# PCB_Preamp_5.net
KiCad netlist of a schematic drawn in EasyEDA Pro
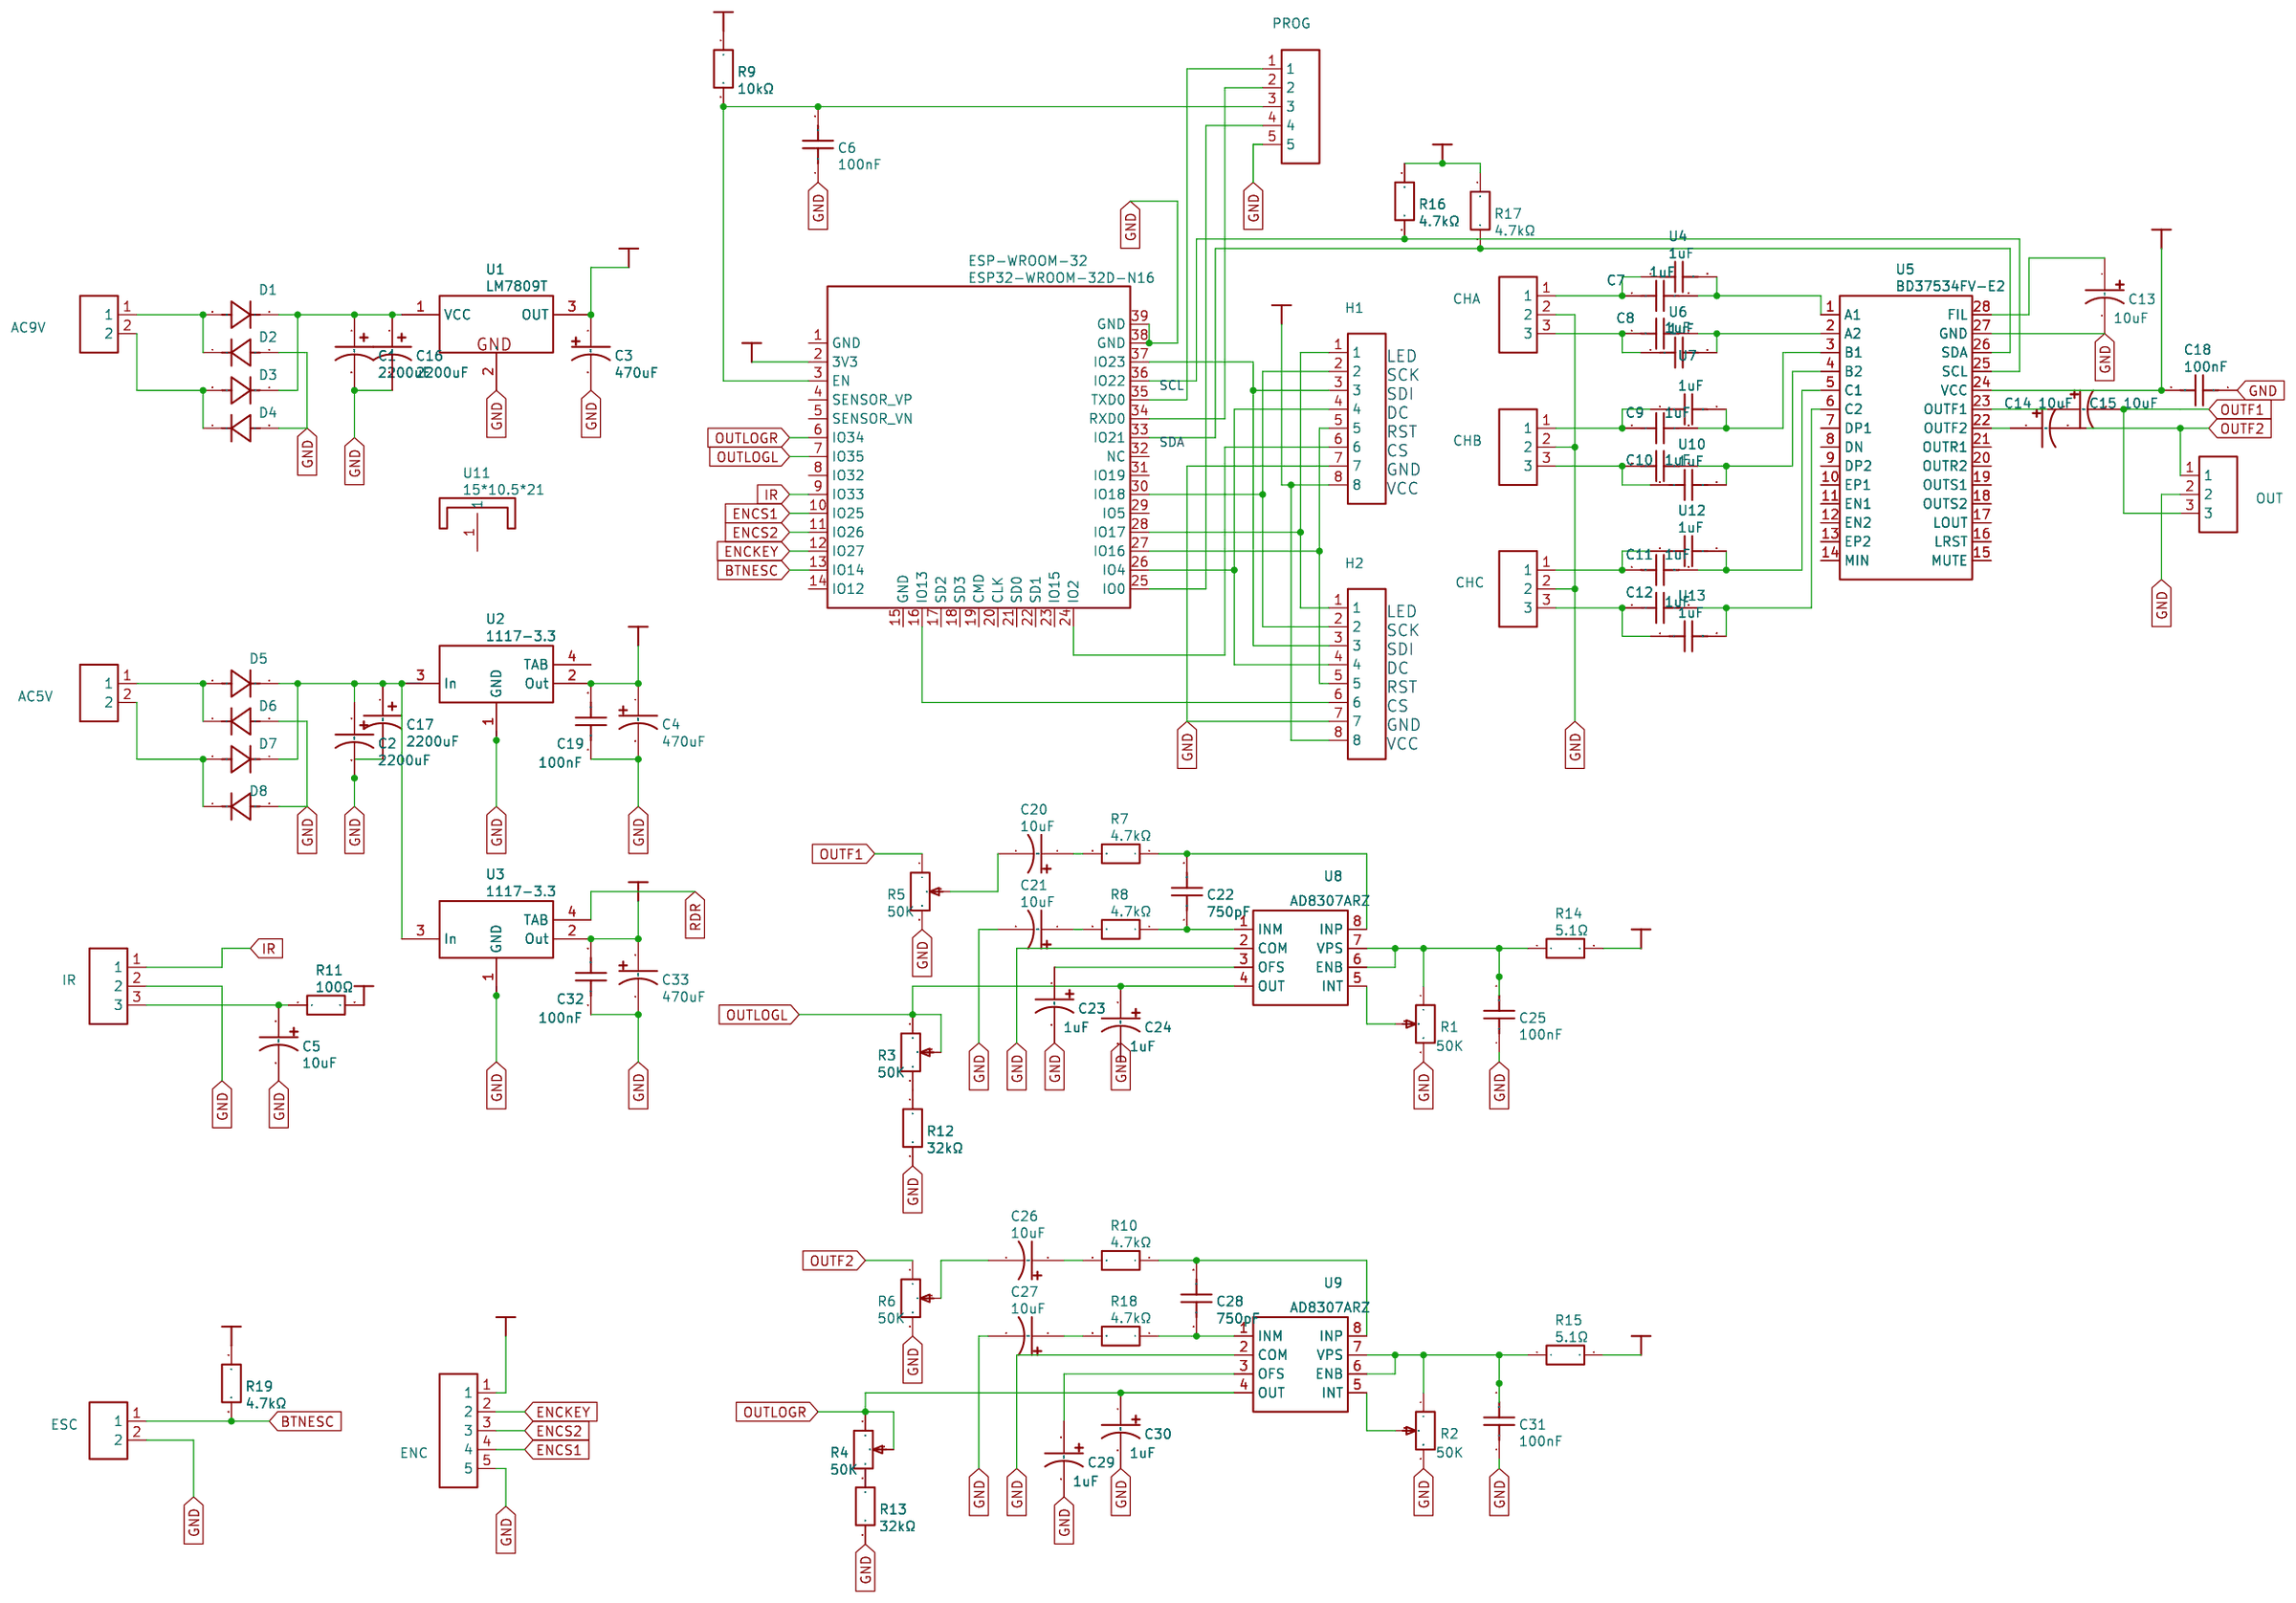
[diagram p0: schematic sheet]

(export (version "E")
  (design (tool "Eeschema 10.0.6"))
  (components
    (comp (ref "AC5V")
      (value "DB126V-5.0-2P")
      (footprint "easyedapro:CONN-TH_2P-P5.00_L7.8-W10.0")
      (fields
        (field (name "Manufacturer Part") "DB126V-5.0-2P-GN-P")
        (field (name "Manufacturer") "DORABO(地博电气)")
      )
      (libsource (lib "easyedapro") (part "DB126V-5.0-2P"))
    )
    (comp (ref "AC9V")
      (value "DB126V-5.0-2P")
      (footprint "easyedapro:CONN-TH_2P-P5.00_L7.8-W10.0")
      (fields
        (field (name "Manufacturer Part") "DB126V-5.0-2P-GN-P")
        (field (name "Manufacturer") "DORABO(地博电气)")
      )
      (libsource (lib "easyedapro") (part "DB126V-5.0-2P"))
    )
    (comp (ref "C1")
      (value "2200uF")
      (footprint "easyedapro:CAP-TH_BD12.5-P5.00-D0.6-FD")
      (fields
        (field (name "Manufacturer Part") "16YXG2200MLLCCE12.5X25")
        (field (name "Manufacturer") "rubycon(红宝石)")
      )
      (libsource (lib "easyedapro") (part "2200uF"))
    )
    (comp (ref "C2")
      (value "2200uF")
      (footprint "easyedapro:CAP-TH_BD12.5-P5.00-D0.6-FD")
      (fields
        (field (name "Manufacturer Part") "16YXG2200MLLCCE12.5X25")
        (field (name "Manufacturer") "rubycon(红宝石)")
      )
      (libsource (lib "easyedapro") (part "2200uF"))
    )
    (comp (ref "C3")
      (value "470uF")
      (footprint "easyedapro:CAP-TH_BD8.0-P3.50-D0.6-FD")
      (fields (field (name "Manufacturer Part") "EHRL474M016F12BC") (field (name "Manufacturer") "HEAO(和澳)"))
      (libsource (lib "easyedapro") (part "470uF"))
    )
    (comp (ref "C4")
      (value "470uF")
      (footprint "easyedapro:CAP-TH_BD8.0-P3.50-D0.6-FD")
      (fields (field (name "Manufacturer Part") "EHRL474M016F12BC") (field (name "Manufacturer") "HEAO(和澳)"))
      (libsource (lib "easyedapro") (part "470uF"))
    )
    (comp (ref "C5")
      (value "10uF")
      (footprint "easyedapro:CAP-TH_BD5.0-P2.00-D0.5-FD")
      (fields (field (name "Manufacturer Part") "35ZLJ47M5X11") (field (name "Manufacturer") "rubycon(红宝石)"))
      (libsource (lib "easyedapro") (part "10uF"))
    )
    (comp (ref "C6")
      (value "100nF")
      (footprint "easyedapro:CAP-TH_L7.2-W2.5-P5.00-D0.6")
      (fields (field (name "Manufacturer Part") "BFC237011104") (field (name "Manufacturer") "VISHAY(威世)"))
      (libsource (lib "easyedapro") (part "100nF"))
    )
    (comp (ref "C7")
      (value "1uF")
      (footprint "easyedapro:CAP-TH_L13.0-W6.0-P10.00-D0.6")
      (fields (field (name "Manufacturer Part") "B32521C1105J") (field (name "Manufacturer") "TDK"))
      (libsource (lib "") (part "1uF_1"))
    )
    (comp (ref "C8")
      (value "1uF")
      (footprint "easyedapro:CAP-TH_L13.0-W6.0-P10.00-D0.6")
      (fields (field (name "Manufacturer Part") "B32521C1105J") (field (name "Manufacturer") "TDK"))
      (libsource (lib "") (part "1uF_1"))
    )
    (comp (ref "C9")
      (value "1uF")
      (footprint "easyedapro:CAP-TH_L13.0-W6.0-P10.00-D0.6")
      (fields (field (name "Manufacturer Part") "B32521C1105J") (field (name "Manufacturer") "TDK"))
      (libsource (lib "") (part "1uF_1"))
    )
    (comp (ref "C10")
      (value "1uF")
      (footprint "easyedapro:CAP-TH_L13.0-W6.0-P10.00-D0.6")
      (fields (field (name "Manufacturer Part") "B32521C1105J") (field (name "Manufacturer") "TDK"))
      (libsource (lib "") (part "1uF_1"))
    )
    (comp (ref "C11")
      (value "1uF")
      (footprint "easyedapro:CAP-TH_L13.0-W6.0-P10.00-D0.6")
      (fields (field (name "Manufacturer Part") "B32521C1105J") (field (name "Manufacturer") "TDK"))
      (libsource (lib "") (part "1uF_1"))
    )
    (comp (ref "C12")
      (value "1uF")
      (footprint "easyedapro:CAP-TH_L13.0-W6.0-P10.00-D0.6")
      (fields (field (name "Manufacturer Part") "B32521C1105J") (field (name "Manufacturer") "TDK"))
      (libsource (lib "") (part "1uF_1"))
    )
    (comp (ref "C13")
      (value "10uF")
      (footprint "easyedapro:CAP-TH_BD5.0-P2.00-D0.5-FD")
      (fields (field (name "Manufacturer Part") "35ZLJ47M5X11") (field (name "Manufacturer") "rubycon(红宝石)"))
      (libsource (lib "easyedapro") (part "10uF"))
    )
    (comp (ref "C14")
      (value "10uF")
      (footprint "easyedapro:CAP-TH_BD5.0-P2.00-D0.5-FD")
      (fields (field (name "Manufacturer Part") "35ZLJ47M5X11") (field (name "Manufacturer") "rubycon(红宝石)"))
      (libsource (lib "") (part "10uF_1"))
    )
    (comp (ref "C15")
      (value "10uF")
      (footprint "easyedapro:CAP-TH_BD5.0-P2.00-D0.5-FD")
      (fields (field (name "Manufacturer Part") "35ZLJ47M5X11") (field (name "Manufacturer") "rubycon(红宝石)"))
      (libsource (lib "") (part "10uF_1"))
    )
    (comp (ref "C16")
      (value "2200uF")
      (footprint "easyedapro:CAP-TH_BD12.5-P5.00-D0.6-FD")
      (fields
        (field (name "Manufacturer Part") "16YXG2200MLLCCE12.5X25")
        (field (name "Manufacturer") "rubycon(红宝石)")
      )
      (libsource (lib "easyedapro") (part "2200uF"))
    )
    (comp (ref "C17")
      (value "2200uF")
      (footprint "easyedapro:CAP-TH_BD12.5-P5.00-D0.6-FD")
      (fields
        (field (name "Manufacturer Part") "16YXG2200MLLCCE12.5X25")
        (field (name "Manufacturer") "rubycon(红宝石)")
      )
      (libsource (lib "easyedapro") (part "2200uF"))
    )
    (comp (ref "C18")
      (value "100nF")
      (footprint "easyedapro:CAP-TH_L7.2-W2.5-P5.00-D0.6")
      (fields (field (name "Manufacturer Part") "BFC237011104") (field (name "Manufacturer") "VISHAY(威世)"))
      (libsource (lib "easyedapro") (part "100nF"))
    )
    (comp (ref "C19")
      (value "100nF")
      (footprint "easyedapro:CAP-TH_L7.2-W2.5-P5.00-D0.6")
      (fields (field (name "Manufacturer Part") "BFC237011104") (field (name "Manufacturer") "VISHAY(威世)"))
      (libsource (lib "easyedapro") (part "100nF"))
    )
    (comp (ref "C20")
      (value "10uF")
      (footprint "easyedapro:CAP-TH_BD5.0-P2.00-D0.5-FD")
      (fields (field (name "Manufacturer Part") "35ZLJ47M5X11") (field (name "Manufacturer") "rubycon(红宝石)"))
      (libsource (lib "") (part "10uF_2"))
    )
    (comp (ref "C21")
      (value "10uF")
      (footprint "easyedapro:CAP-TH_BD5.0-P2.00-D0.5-FD")
      (fields (field (name "Manufacturer Part") "35ZLJ47M5X11") (field (name "Manufacturer") "rubycon(红宝石)"))
      (libsource (lib "") (part "10uF_2"))
    )
    (comp (ref "C22")
      (value "750pF")
      (footprint "easyedapro:CAP-TH_L5.0-W2.5-P5.08-D0.7")
      (fields
        (field (name "Manufacturer Part") "RPE5C1H681J2S1A03A")
        (field (name "Manufacturer") "muRata(村田)")
      )
      (libsource (lib "easyedapro") (part "750pF"))
    )
    (comp (ref "C23")
      (value "1uF")
      (footprint "easyedapro:CAP-TH_BD5.0-P2.00-D0.5-FD")
      (fields (field (name "Manufacturer Part") "35ZLJ47M5X11") (field (name "Manufacturer") "rubycon(红宝石)"))
      (libsource (lib "easyedapro") (part "1uF"))
    )
    (comp (ref "C24")
      (value "1uF")
      (footprint "easyedapro:CAP-TH_BD5.0-P2.00-D0.5-FD")
      (fields (field (name "Manufacturer Part") "35ZLJ47M5X11") (field (name "Manufacturer") "rubycon(红宝石)"))
      (libsource (lib "easyedapro") (part "1uF"))
    )
    (comp (ref "C25")
      (value "100nF")
      (footprint "easyedapro:CAP-TH_L7.2-W2.5-P5.00-D0.6")
      (fields (field (name "Manufacturer Part") "BFC237011104") (field (name "Manufacturer") "VISHAY(威世)"))
      (libsource (lib "easyedapro") (part "100nF"))
    )
    (comp (ref "C26")
      (value "10uF")
      (footprint "easyedapro:CAP-TH_BD5.0-P2.00-D0.5-FD")
      (fields (field (name "Manufacturer Part") "35ZLJ47M5X11") (field (name "Manufacturer") "rubycon(红宝石)"))
      (libsource (lib "") (part "10uF_2"))
    )
    (comp (ref "C27")
      (value "10uF")
      (footprint "easyedapro:CAP-TH_BD5.0-P2.00-D0.5-FD")
      (fields (field (name "Manufacturer Part") "35ZLJ47M5X11") (field (name "Manufacturer") "rubycon(红宝石)"))
      (libsource (lib "") (part "10uF_2"))
    )
    (comp (ref "C28")
      (value "750pF")
      (footprint "easyedapro:CAP-TH_L5.0-W2.5-P5.08-D0.7")
      (fields
        (field (name "Manufacturer Part") "RPE5C1H681J2S1A03A")
        (field (name "Manufacturer") "muRata(村田)")
      )
      (libsource (lib "easyedapro") (part "750pF"))
    )
    (comp (ref "C29")
      (value "1uF")
      (footprint "easyedapro:CAP-TH_BD5.0-P2.00-D0.5-FD")
      (fields (field (name "Manufacturer Part") "35ZLJ47M5X11") (field (name "Manufacturer") "rubycon(红宝石)"))
      (libsource (lib "easyedapro") (part "1uF"))
    )
    (comp (ref "C30")
      (value "1uF")
      (footprint "easyedapro:CAP-TH_BD5.0-P2.00-D0.5-FD")
      (fields (field (name "Manufacturer Part") "35ZLJ47M5X11") (field (name "Manufacturer") "rubycon(红宝石)"))
      (libsource (lib "easyedapro") (part "1uF"))
    )
    (comp (ref "C31")
      (value "100nF")
      (footprint "easyedapro:CAP-TH_L7.2-W2.5-P5.00-D0.6")
      (fields (field (name "Manufacturer Part") "BFC237011104") (field (name "Manufacturer") "VISHAY(威世)"))
      (libsource (lib "easyedapro") (part "100nF"))
    )
    (comp (ref "C32")
      (value "100nF")
      (footprint "easyedapro:CAP-TH_L7.2-W2.5-P5.00-D0.6")
      (fields (field (name "Manufacturer Part") "BFC237011104") (field (name "Manufacturer") "VISHAY(威世)"))
      (libsource (lib "easyedapro") (part "100nF"))
    )
    (comp (ref "C33")
      (value "470uF")
      (footprint "easyedapro:CAP-TH_BD8.0-P3.50-D0.6-FD")
      (fields (field (name "Manufacturer Part") "EHRL474M016F12BC") (field (name "Manufacturer") "HEAO(和澳)"))
      (libsource (lib "easyedapro") (part "470uF"))
    )
    (comp (ref "CHA")
      (value "ZX-HA2.54-3PZZ")
      (footprint "easyedapro:CONN-TH_XH-3A")
      (fields (field (name "Manufacturer") "Megastar(兆星)"))
      (libsource (lib "easyedapro") (part "ZX-HA2.54-3PZZ"))
    )
    (comp (ref "CHB")
      (value "ZX-HA2.54-3PZZ")
      (footprint "easyedapro:CONN-TH_XH-3A")
      (fields (field (name "Manufacturer") "Megastar(兆星)"))
      (libsource (lib "easyedapro") (part "ZX-HA2.54-3PZZ"))
    )
    (comp (ref "CHC")
      (value "ZX-HA2.54-3PZZ")
      (footprint "easyedapro:CONN-TH_XH-3A")
      (fields (field (name "Manufacturer") "Megastar(兆星)"))
      (libsource (lib "easyedapro") (part "ZX-HA2.54-3PZZ"))
    )
    (comp (ref "D1")
      (value "S1D_C840837")
      (footprint "easyedapro:SMA_L4.3-W2.6-LS5.0-RD")
      (fields (field (name "Manufacturer Part") "S1D") (field (name "Manufacturer") "MDD(辰达半导体)"))
      (libsource (lib "easyedapro") (part "S1D_C840837"))
    )
    (comp (ref "D2")
      (value "S1D_C840837")
      (footprint "easyedapro:SMA_L4.3-W2.6-LS5.0-RD")
      (fields (field (name "Manufacturer Part") "S1D") (field (name "Manufacturer") "MDD(辰达半导体)"))
      (libsource (lib "easyedapro") (part "S1D_C840837"))
    )
    (comp (ref "D3")
      (value "S1D_C840837")
      (footprint "easyedapro:SMA_L4.3-W2.6-LS5.0-RD")
      (fields (field (name "Manufacturer Part") "S1D") (field (name "Manufacturer") "MDD(辰达半导体)"))
      (libsource (lib "easyedapro") (part "S1D_C840837"))
    )
    (comp (ref "D4")
      (value "S1D_C840837")
      (footprint "easyedapro:SMA_L4.3-W2.6-LS5.0-RD")
      (fields (field (name "Manufacturer Part") "S1D") (field (name "Manufacturer") "MDD(辰达半导体)"))
      (libsource (lib "easyedapro") (part "S1D_C840837"))
    )
    (comp (ref "D5")
      (value "S1D_C840837")
      (footprint "easyedapro:SMA_L4.3-W2.6-LS5.0-RD")
      (fields (field (name "Manufacturer Part") "S1D") (field (name "Manufacturer") "MDD(辰达半导体)"))
      (libsource (lib "easyedapro") (part "S1D_C840837"))
    )
    (comp (ref "D6")
      (value "S1D_C840837")
      (footprint "easyedapro:SMA_L4.3-W2.6-LS5.0-RD")
      (fields (field (name "Manufacturer Part") "S1D") (field (name "Manufacturer") "MDD(辰达半导体)"))
      (libsource (lib "easyedapro") (part "S1D_C840837"))
    )
    (comp (ref "D7")
      (value "S1D_C840837")
      (footprint "easyedapro:SMA_L4.3-W2.6-LS5.0-RD")
      (fields (field (name "Manufacturer Part") "S1D") (field (name "Manufacturer") "MDD(辰达半导体)"))
      (libsource (lib "easyedapro") (part "S1D_C840837"))
    )
    (comp (ref "D8")
      (value "S1D_C840837")
      (footprint "easyedapro:SMA_L4.3-W2.6-LS5.0-RD")
      (fields (field (name "Manufacturer Part") "S1D") (field (name "Manufacturer") "MDD(辰达半导体)"))
      (libsource (lib "easyedapro") (part "S1D_C840837"))
    )
    (comp (ref "ENC")
      (value "HC-XH-5A-G")
      (footprint "easyedapro:CONN-TH_5P-P2.50_HC-XH-5A-G")
      (fields (field (name "Manufacturer") "HCTL(华灿天禄)"))
      (libsource (lib "easyedapro") (part "HC-XH-5A-G"))
    )
    (comp (ref "ESC")
      (value "XH-D-2A")
      (footprint "easyedapro:CONN-TH_XH-2A")
      (fields (field (name "Manufacturer") "DEALON(德艺隆)"))
      (libsource (lib "easyedapro") (part "XH-D-2A"))
    )
    (comp (ref "ESP-WROOM-32")
      (value "ESP32-WROOM-32D-N16")
      (footprint "easyedapro:WIFIM-SMD_ESP32-WROOM-32D")
      (fields (field (name "Manufacturer Part") "ESP32-WROOM-32D-N16-被合并"))
      (libsource (lib "easyedapro") (part "ESP32-WROOM-32D-N16"))
    )
    (comp (ref "H1")
      (value "61300811121")
      (footprint "easyedapro:HDR-TH_8P-P2.54-V-M")
      (fields (field (name "Manufacturer") "Wurth(伍尔特)"))
      (libsource (lib "easyedapro") (part "61300811121"))
    )
    (comp (ref "H2")
      (value "61300811121")
      (footprint "easyedapro:HDR-TH_8P-P2.54-V-M")
      (fields (field (name "Manufacturer") "Wurth(伍尔特)"))
      (libsource (lib "easyedapro") (part "61300811121"))
    )
    (comp (ref "IR")
      (value "ZX-HA2.54-3PZZ")
      (footprint "easyedapro:CONN-TH_XH-3A")
      (fields (field (name "Manufacturer") "Megastar(兆星)"))
      (libsource (lib "easyedapro") (part "ZX-HA2.54-3PZZ"))
    )
    (comp (ref "OUT")
      (value "ZX-HA2.54-3PZZ")
      (footprint "easyedapro:CONN-TH_XH-3A")
      (fields (field (name "Manufacturer") "Megastar(兆星)"))
      (libsource (lib "") (part "ZX-HA2.54-3PZZ_1"))
    )
    (comp (ref "PROG")
      (value "HC-PZ254-11.5L-1X5PZ")
      (footprint "easyedapro:HDR-TH_5P-P2.54-V-M")
      (fields
        (field (name "Manufacturer Part") "HC-PZ254-11.5L-1x5PZ")
        (field (name "Manufacturer") "HC(虹成电子)")
      )
      (libsource (lib "easyedapro") (part "HC-PZ254-11.5L-1X5PZ"))
    )
    (comp (ref "R1")
      (value "50K")
      (footprint "easyedapro:RES-ADJ-SMD_RM065-V1")
      (fields (field (name "Manufacturer Part") "蓝白可调电阻 RM065-V1-102"))
      (libsource (lib "easyedapro") (part "50K"))
    )
    (comp (ref "R2")
      (value "50K")
      (footprint "easyedapro:RES-ADJ-SMD_RM065-V1")
      (fields (field (name "Manufacturer Part") "蓝白可调电阻 RM065-V1-102"))
      (libsource (lib "easyedapro") (part "50K"))
    )
    (comp (ref "R3")
      (value "50K")
      (footprint "easyedapro:RES-ADJ-SMD_RM065-V1")
      (fields (field (name "Manufacturer Part") "蓝白可调电阻 RM065-V1-102"))
      (libsource (lib "") (part "50K_1"))
    )
    (comp (ref "R4")
      (value "50K")
      (footprint "easyedapro:RES-ADJ-SMD_RM065-V1")
      (fields (field (name "Manufacturer Part") "蓝白可调电阻 RM065-V1-102"))
      (libsource (lib "") (part "50K_1"))
    )
    (comp (ref "R5")
      (value "50K")
      (footprint "easyedapro:RES-ADJ-SMD_RM065-V1")
      (fields (field (name "Manufacturer Part") "蓝白可调电阻 RM065-V1-102"))
      (libsource (lib "") (part "50K_1"))
    )
    (comp (ref "R6")
      (value "50K")
      (footprint "easyedapro:RES-ADJ-SMD_RM065-V1")
      (fields (field (name "Manufacturer Part") "蓝白可调电阻 RM065-V1-102"))
      (libsource (lib "") (part "50K_1"))
    )
    (comp (ref "R7")
      (value "4.7kΩ")
      (footprint "easyedapro:R1206")
      (fields (field (name "Manufacturer Part") "CR1/8W-4K7±5%-ST26") (field (name "Manufacturer") "VO(翔胜)"))
      (libsource (lib "easyedapro") (part "4.7kΩ"))
    )
    (comp (ref "R8")
      (value "4.7kΩ")
      (footprint "easyedapro:R1206")
      (fields (field (name "Manufacturer Part") "CR1/8W-4K7±5%-ST26") (field (name "Manufacturer") "VO(翔胜)"))
      (libsource (lib "easyedapro") (part "4.7kΩ"))
    )
    (comp (ref "R9")
      (value "10kΩ")
      (footprint "easyedapro:R1206")
      (fields (field (name "Manufacturer Part") "CR1/8W-4K7±5%-ST26") (field (name "Manufacturer") "VO(翔胜)"))
      (libsource (lib "easyedapro") (part "10kΩ"))
    )
    (comp (ref "R10")
      (value "4.7kΩ")
      (footprint "easyedapro:R1206")
      (fields (field (name "Manufacturer Part") "CR1/8W-4K7±5%-ST26") (field (name "Manufacturer") "VO(翔胜)"))
      (libsource (lib "easyedapro") (part "4.7kΩ"))
    )
    (comp (ref "R11")
      (value "100Ω")
      (footprint "easyedapro:R1206")
      (fields (field (name "Manufacturer Part") "CR1/8W-4K7±5%-ST26") (field (name "Manufacturer") "VO(翔胜)"))
      (libsource (lib "easyedapro") (part "100Ω"))
    )
    (comp (ref "R12")
      (value "32kΩ")
      (footprint "easyedapro:R1206")
      (fields (field (name "Manufacturer Part") "CR1/8W-4K7±5%-ST26") (field (name "Manufacturer") "VO(翔胜)"))
      (libsource (lib "easyedapro") (part "32kΩ"))
    )
    (comp (ref "R13")
      (value "32kΩ")
      (footprint "easyedapro:R1206")
      (fields (field (name "Manufacturer Part") "CR1/8W-4K7±5%-ST26") (field (name "Manufacturer") "VO(翔胜)"))
      (libsource (lib "easyedapro") (part "32kΩ"))
    )
    (comp (ref "R14")
      (value "5.1Ω")
      (footprint "easyedapro:R1206")
      (fields (field (name "Manufacturer Part") "CR1/8W-4K7±5%-ST26") (field (name "Manufacturer") "VO(翔胜)"))
      (libsource (lib "easyedapro") (part "5.1Ω"))
    )
    (comp (ref "R15")
      (value "5.1Ω")
      (footprint "easyedapro:R1206")
      (fields (field (name "Manufacturer Part") "CR1/8W-4K7±5%-ST26") (field (name "Manufacturer") "VO(翔胜)"))
      (libsource (lib "easyedapro") (part "5.1Ω"))
    )
    (comp (ref "R16")
      (value "4.7kΩ")
      (footprint "easyedapro:R1206")
      (fields (field (name "Manufacturer Part") "CR1/8W-4K7±5%-ST26") (field (name "Manufacturer") "VO(翔胜)"))
      (libsource (lib "") (part "4.7kΩ_1"))
    )
    (comp (ref "R17")
      (value "4.7kΩ")
      (footprint "easyedapro:R1206")
      (fields (field (name "Manufacturer Part") "CR1/8W-4K7±5%-ST26") (field (name "Manufacturer") "VO(翔胜)"))
      (libsource (lib "") (part "4.7kΩ_1"))
    )
    (comp (ref "R18")
      (value "4.7kΩ")
      (footprint "easyedapro:R1206")
      (fields (field (name "Manufacturer Part") "CR1/8W-4K7±5%-ST26") (field (name "Manufacturer") "VO(翔胜)"))
      (libsource (lib "easyedapro") (part "4.7kΩ"))
    )
    (comp (ref "R19")
      (value "4.7kΩ")
      (footprint "easyedapro:R1206")
      (fields (field (name "Manufacturer Part") "CR1/8W-4K7±5%-ST26") (field (name "Manufacturer") "VO(翔胜)"))
      (libsource (lib "") (part "4.7kΩ_1"))
    )
    (comp (ref "U1")
      (value "LM7809T")
      (footprint "easyedapro:TO-220-3_L10.0-W4.5-P2.54-L")
      (fields (field (name "Manufacturer") "HGSEMI(华冠)"))
      (libsource (lib "easyedapro") (part "LM7809T"))
    )
    (comp (ref "U2")
      (value "1117-3.3")
      (footprint "easyedapro:SOT-223-3_L6.4-W3.5-P2.30-LS7.0-BR")
      (fields (field (name "Manufacturer") "IDCHIP(英锐芯)"))
      (libsource (lib "easyedapro") (part "1117-3.3"))
    )
    (comp (ref "U3")
      (value "1117-3.3")
      (footprint "easyedapro:SOT-223-3_L6.4-W3.5-P2.30-LS7.0-BR")
      (fields (field (name "Manufacturer") "IDCHIP(英锐芯)"))
      (libsource (lib "easyedapro") (part "1117-3.3"))
    )
    (comp (ref "U4")
      (value "1uF")
      (footprint "easyedapro:CAP-TH_L13.0-W6.0-P10.00-D0.6")
      (fields (field (name "Manufacturer Part") "B32521C1105J") (field (name "Manufacturer") "TDK"))
      (libsource (lib "") (part "1uF_1"))
    )
    (comp (ref "U5")
      (value "BD37534FV-E2")
      (footprint "easyedapro:SSOP-28_L10.4-W5.6-P0.65-LS7.6-BL")
      (fields (field (name "Manufacturer") "ROHM(罗姆)"))
      (libsource (lib "easyedapro") (part "BD37534FV-E2"))
    )
    (comp (ref "U6")
      (value "1uF")
      (footprint "easyedapro:CAP-TH_L13.0-W6.0-P10.00-D0.6")
      (fields (field (name "Manufacturer Part") "B32521C1105J") (field (name "Manufacturer") "TDK"))
      (libsource (lib "") (part "1uF_1"))
    )
    (comp (ref "U7")
      (value "1uF")
      (footprint "easyedapro:CAP-TH_L13.0-W6.0-P10.00-D0.6")
      (fields (field (name "Manufacturer Part") "B32521C1105J") (field (name "Manufacturer") "TDK"))
      (libsource (lib "") (part "1uF_1"))
    )
    (comp (ref "U8")
      (value "AD8307ARZ")
      (footprint "easyedapro:SOIC-8_L4.9-W3.9-P1.27-LS6.0-BL")
      (fields (field (name "Manufacturer") "ADI(亚德诺)/LINEAR(凌特)"))
      (libsource (lib "easyedapro") (part "AD8307ARZ"))
    )
    (comp (ref "U9")
      (value "AD8307ARZ")
      (footprint "easyedapro:SOIC-8_L4.9-W3.9-P1.27-LS6.0-BL")
      (fields (field (name "Manufacturer") "ADI(亚德诺)/LINEAR(凌特)"))
      (libsource (lib "easyedapro") (part "AD8307ARZ"))
    )
    (comp (ref "U10")
      (value "1uF")
      (footprint "easyedapro:CAP-TH_L13.0-W6.0-P10.00-D0.6")
      (fields (field (name "Manufacturer Part") "B32521C1105J") (field (name "Manufacturer") "TDK"))
      (libsource (lib "") (part "1uF_1"))
    )
    (comp (ref "U11")
      (value "15*10.5*21")
      (footprint "easyedapro:SINK-TH_L15.0-W10.5-H21.0")
      (fields (field (name "Manufacturer Part") "15.5*10.5*21") (field (name "Manufacturer") "XSD(鑫顺达)"))
      (libsource (lib "easyedapro") (part "15*10.5*21"))
    )
    (comp (ref "U12")
      (value "1uF")
      (footprint "easyedapro:CAP-TH_L13.0-W6.0-P10.00-D0.6")
      (fields (field (name "Manufacturer Part") "B32521C1105J") (field (name "Manufacturer") "TDK"))
      (libsource (lib "") (part "1uF_1"))
    )
    (comp (ref "U13")
      (value "1uF")
      (footprint "easyedapro:CAP-TH_L13.0-W6.0-P10.00-D0.6")
      (fields (field (name "Manufacturer Part") "B32521C1105J") (field (name "Manufacturer") "TDK"))
      (libsource (lib "") (part "1uF_1"))
    )
  )
  (nets
    (net (code "1") (name "+3V3") (class "Default")
      (node (ref "C19") (pin "2") (pinfunction "2_2") (pintype "unspecified"))
      (node (ref "C4") (pin "1") (pinfunction "1_1") (pintype "unspecified"))
      (node (ref "R14") (pin "2") (pinfunction "2_2") (pintype "unspecified"))
      (node (ref "R15") (pin "2") (pinfunction "2_2") (pintype "unspecified"))
      (node (ref "U2") (pin "2") (pinfunction "Out_2") (pintype "unspecified"))
    )
    (net (code "2") (name "+3V3D") (class "Default")
      (node (ref "C32") (pin "2") (pinfunction "2_2") (pintype "unspecified"))
      (node (ref "C33") (pin "1") (pinfunction "1_1") (pintype "unspecified"))
      (node (ref "ENC") (pin "1") (pinfunction "1_1") (pintype "unspecified"))
      (node (ref "ESP-WROOM-32") (pin "2") (pinfunction "3V3_2") (pintype "unspecified"))
      (node (ref "H1") (pin "8") (pinfunction "8_8") (pintype "unspecified"))
      (node (ref "H2") (pin "8") (pinfunction "8_8") (pintype "unspecified"))
      (node (ref "R11") (pin "2") (pinfunction "2_2") (pintype "unspecified"))
      (node (ref "R16") (pin "1") (pinfunction "1_1") (pintype "unspecified"))
      (node (ref "R17") (pin "1") (pinfunction "1_1") (pintype "unspecified"))
      (node (ref "R19") (pin "1") (pinfunction "1_1") (pintype "unspecified"))
      (node (ref "R9") (pin "1") (pinfunction "1_1") (pintype "unspecified"))
      (node (ref "U3") (pin "2") (pinfunction "Out_2") (pintype "unspecified"))
    )
    (net (code "3") (name "+9V") (class "Default")
      (node (ref "C18") (pin "2") (pinfunction "2_2") (pintype "unspecified"))
      (node (ref "C3") (pin "1") (pinfunction "1_1") (pintype "unspecified"))
      (node (ref "U1") (pin "3") (pinfunction "OUT_3") (pintype "unspecified"))
      (node (ref "U5") (pin "24") (pinfunction "VCC_24") (pintype "unspecified"))
    )
    (net (code "4") (name "BTNESC") (class "Default")
      (node (ref "ESC") (pin "1") (pinfunction "1_1") (pintype "unspecified"))
      (node (ref "ESP-WROOM-32") (pin "13") (pinfunction "IO14_13") (pintype "unspecified"))
      (node (ref "R19") (pin "2") (pinfunction "2_2") (pintype "unspecified"))
    )
    (net (code "5") (name "ENCKEY") (class "Default")
      (node (ref "ENC") (pin "2") (pinfunction "2_2") (pintype "unspecified"))
      (node (ref "ESP-WROOM-32") (pin "12") (pinfunction "IO27_12") (pintype "unspecified"))
    )
    (net (code "6") (name "ENCS1") (class "Default")
      (node (ref "ENC") (pin "4") (pinfunction "4_4") (pintype "unspecified"))
      (node (ref "ESP-WROOM-32") (pin "10") (pinfunction "IO25_10") (pintype "unspecified"))
    )
    (net (code "7") (name "ENCS2") (class "Default")
      (node (ref "ENC") (pin "3") (pinfunction "3_3") (pintype "unspecified"))
      (node (ref "ESP-WROOM-32") (pin "11") (pinfunction "IO26_11") (pintype "unspecified"))
    )
    (net (code "8") (name "GND") (class "Default")
      (node (ref "C1") (pin "2") (pinfunction "2_2") (pintype "unspecified"))
      (node (ref "C13") (pin "2") (pinfunction "2_2") (pintype "unspecified"))
      (node (ref "C16") (pin "2") (pinfunction "2_2") (pintype "unspecified"))
      (node (ref "C17") (pin "2") (pinfunction "2_2") (pintype "unspecified"))
      (node (ref "C18") (pin "1") (pinfunction "1_1") (pintype "unspecified"))
      (node (ref "C19") (pin "1") (pinfunction "1_1") (pintype "unspecified"))
      (node (ref "C2") (pin "2") (pinfunction "2_2") (pintype "unspecified"))
      (node (ref "C21") (pin "2") (pinfunction "2_2") (pintype "unspecified"))
      (node (ref "C23") (pin "2") (pinfunction "2_2") (pintype "unspecified"))
      (node (ref "C24") (pin "2") (pinfunction "2_2") (pintype "unspecified"))
      (node (ref "C25") (pin "1") (pinfunction "1_1") (pintype "unspecified"))
      (node (ref "C27") (pin "2") (pinfunction "2_2") (pintype "unspecified"))
      (node (ref "C29") (pin "2") (pinfunction "2_2") (pintype "unspecified"))
      (node (ref "C3") (pin "2") (pinfunction "2_2") (pintype "unspecified"))
      (node (ref "C30") (pin "2") (pinfunction "2_2") (pintype "unspecified"))
      (node (ref "C31") (pin "1") (pinfunction "1_1") (pintype "unspecified"))
      (node (ref "C32") (pin "1") (pinfunction "1_1") (pintype "unspecified"))
      (node (ref "C33") (pin "2") (pinfunction "2_2") (pintype "unspecified"))
      (node (ref "C4") (pin "2") (pinfunction "2_2") (pintype "unspecified"))
      (node (ref "C5") (pin "2") (pinfunction "2_2") (pintype "unspecified"))
      (node (ref "C6") (pin "1") (pinfunction "1_1") (pintype "unspecified"))
      (node (ref "CHA") (pin "2") (pinfunction "2_2") (pintype "unspecified"))
      (node (ref "CHB") (pin "2") (pinfunction "2_2") (pintype "unspecified"))
      (node (ref "CHC") (pin "2") (pinfunction "2_2") (pintype "unspecified"))
      (node (ref "D2") (pin "2") (pinfunction "A_2") (pintype "unspecified"))
      (node (ref "D4") (pin "2") (pinfunction "A_2") (pintype "unspecified"))
      (node (ref "D6") (pin "2") (pinfunction "A_2") (pintype "unspecified"))
      (node (ref "D8") (pin "2") (pinfunction "A_2") (pintype "unspecified"))
      (node (ref "ENC") (pin "5") (pinfunction "5_5") (pintype "unspecified"))
      (node (ref "ESC") (pin "2") (pinfunction "2_2") (pintype "unspecified"))
      (node (ref "ESP-WROOM-32") (pin "38") (pinfunction "GND_38") (pintype "unspecified"))
      (node (ref "ESP-WROOM-32") (pin "39") (pinfunction "GND_39") (pintype "unspecified"))
      (node (ref "H1") (pin "7") (pinfunction "7_7") (pintype "unspecified"))
      (node (ref "H2") (pin "7") (pinfunction "7_7") (pintype "unspecified"))
      (node (ref "IR") (pin "2") (pinfunction "2_2") (pintype "unspecified"))
      (node (ref "OUT") (pin "2") (pinfunction "2_2") (pintype "unspecified"))
      (node (ref "PROG") (pin "5") (pinfunction "5_5") (pintype "unspecified"))
      (node (ref "R1") (pin "3") (pinfunction "3_3") (pintype "input"))
      (node (ref "R12") (pin "2") (pinfunction "2_2") (pintype "unspecified"))
      (node (ref "R13") (pin "2") (pinfunction "2_2") (pintype "unspecified"))
      (node (ref "R2") (pin "3") (pinfunction "3_3") (pintype "input"))
      (node (ref "R5") (pin "3") (pinfunction "3_3") (pintype "input"))
      (node (ref "R6") (pin "3") (pinfunction "3_3") (pintype "input"))
      (node (ref "U1") (pin "2") (pinfunction "GND_2") (pintype "unspecified"))
      (node (ref "U2") (pin "1") (pinfunction "GND_1") (pintype "unspecified"))
      (node (ref "U3") (pin "1") (pinfunction "GND_1") (pintype "unspecified"))
      (node (ref "U5") (pin "27") (pinfunction "GND_27") (pintype "unspecified"))
      (node (ref "U8") (pin "2") (pinfunction "COM_2") (pintype "unspecified"))
      (node (ref "U9") (pin "2") (pinfunction "COM_2") (pintype "unspecified"))
    )
    (net (code "9") (name "IR") (class "Default")
      (node (ref "ESP-WROOM-32") (pin "9") (pinfunction "IO33_9") (pintype "unspecified"))
      (node (ref "IR") (pin "1") (pinfunction "1_1") (pintype "unspecified"))
    )
    (net (code "10") (name "Net-(C5-Pad1)") (class "Default")
      (node (ref "C5") (pin "1") (pinfunction "1_1") (pintype "unspecified"))
      (node (ref "IR") (pin "3") (pinfunction "3_3") (pintype "unspecified"))
      (node (ref "R11") (pin "1") (pinfunction "1_1") (pintype "unspecified"))
    )
    (net (code "11") (name "Net-(C7-Pad1)") (class "Default")
      (node (ref "C7") (pin "1") (pinfunction "1_1") (pintype "unspecified"))
      (node (ref "CHA") (pin "1") (pinfunction "1_1") (pintype "unspecified"))
      (node (ref "U4") (pin "1") (pinfunction "1_1") (pintype "unspecified"))
    )
    (net (code "12") (name "Net-(C8-Pad1)") (class "Default")
      (node (ref "C8") (pin "1") (pinfunction "1_1") (pintype "unspecified"))
      (node (ref "CHA") (pin "3") (pinfunction "3_3") (pintype "unspecified"))
      (node (ref "U6") (pin "1") (pinfunction "1_1") (pintype "unspecified"))
    )
    (net (code "13") (name "Net-(C9-Pad1)") (class "Default")
      (node (ref "C9") (pin "1") (pinfunction "1_1") (pintype "unspecified"))
      (node (ref "CHB") (pin "1") (pinfunction "1_1") (pintype "unspecified"))
      (node (ref "U7") (pin "1") (pinfunction "1_1") (pintype "unspecified"))
    )
    (net (code "14") (name "Net-(C10-Pad1)") (class "Default")
      (node (ref "C10") (pin "1") (pinfunction "1_1") (pintype "unspecified"))
      (node (ref "CHB") (pin "3") (pinfunction "3_3") (pintype "unspecified"))
      (node (ref "U10") (pin "1") (pinfunction "1_1") (pintype "unspecified"))
    )
    (net (code "15") (name "Net-(C11-Pad1)") (class "Default")
      (node (ref "C11") (pin "1") (pinfunction "1_1") (pintype "unspecified"))
      (node (ref "CHC") (pin "1") (pinfunction "1_1") (pintype "unspecified"))
      (node (ref "U12") (pin "1") (pinfunction "1_1") (pintype "unspecified"))
    )
    (net (code "16") (name "Net-(C12-Pad1)") (class "Default")
      (node (ref "C12") (pin "1") (pinfunction "1_1") (pintype "unspecified"))
      (node (ref "CHC") (pin "3") (pinfunction "3_3") (pintype "unspecified"))
      (node (ref "U13") (pin "1") (pinfunction "1_1") (pintype "unspecified"))
    )
    (net (code "17") (name "Net-(C20-Pad1)") (class "Default")
      (node (ref "C20") (pin "1") (pinfunction "1_1") (pintype "unspecified"))
      (node (ref "R7") (pin "2") (pinfunction "2_2") (pintype "unspecified"))
    )
    (net (code "18") (name "Net-(C20-Pad2)") (class "Default")
      (node (ref "C20") (pin "2") (pinfunction "2_2") (pintype "unspecified"))
      (node (ref "R5") (pin "2") (pinfunction "2_2") (pintype "input"))
    )
    (net (code "19") (name "Net-(C21-Pad1)") (class "Default")
      (node (ref "C21") (pin "1") (pinfunction "1_1") (pintype "unspecified"))
      (node (ref "R8") (pin "2") (pinfunction "2_2") (pintype "unspecified"))
    )
    (net (code "20") (name "Net-(C26-Pad1)") (class "Default")
      (node (ref "C26") (pin "1") (pinfunction "1_1") (pintype "unspecified"))
      (node (ref "R10") (pin "2") (pinfunction "2_2") (pintype "unspecified"))
    )
    (net (code "21") (name "Net-(C26-Pad2)") (class "Default")
      (node (ref "C26") (pin "2") (pinfunction "2_2") (pintype "unspecified"))
      (node (ref "R6") (pin "2") (pinfunction "2_2") (pintype "input"))
    )
    (net (code "22") (name "Net-(C27-Pad1)") (class "Default")
      (node (ref "C27") (pin "1") (pinfunction "1_1") (pintype "unspecified"))
      (node (ref "R18") (pin "2") (pinfunction "2_2") (pintype "unspecified"))
    )
    (net (code "23") (name "Net-(D1-A)") (class "Default")
      (node (ref "AC9V") (pin "1") (pinfunction "1_1") (pintype "unspecified"))
      (node (ref "D1") (pin "2") (pinfunction "A_2") (pintype "unspecified"))
      (node (ref "D2") (pin "1") (pinfunction "K_1") (pintype "unspecified"))
    )
    (net (code "24") (name "Net-(D1-K)") (class "Default")
      (node (ref "C1") (pin "1") (pinfunction "1_1") (pintype "unspecified"))
      (node (ref "C16") (pin "1") (pinfunction "1_1") (pintype "unspecified"))
      (node (ref "D1") (pin "1") (pinfunction "K_1") (pintype "unspecified"))
      (node (ref "D3") (pin "1") (pinfunction "K_1") (pintype "unspecified"))
      (node (ref "U1") (pin "1") (pinfunction "VCC_1") (pintype "unspecified"))
    )
    (net (code "25") (name "Net-(D3-A)") (class "Default")
      (node (ref "AC9V") (pin "2") (pinfunction "2_2") (pintype "unspecified"))
      (node (ref "D3") (pin "2") (pinfunction "A_2") (pintype "unspecified"))
      (node (ref "D4") (pin "1") (pinfunction "K_1") (pintype "unspecified"))
    )
    (net (code "26") (name "Net-(D5-A)") (class "Default")
      (node (ref "AC5V") (pin "1") (pinfunction "1_1") (pintype "unspecified"))
      (node (ref "D5") (pin "2") (pinfunction "A_2") (pintype "unspecified"))
      (node (ref "D6") (pin "1") (pinfunction "K_1") (pintype "unspecified"))
    )
    (net (code "27") (name "Net-(D5-K)") (class "Default")
      (node (ref "C17") (pin "1") (pinfunction "1_1") (pintype "unspecified"))
      (node (ref "C2") (pin "1") (pinfunction "1_1") (pintype "unspecified"))
      (node (ref "D5") (pin "1") (pinfunction "K_1") (pintype "unspecified"))
      (node (ref "D7") (pin "1") (pinfunction "K_1") (pintype "unspecified"))
      (node (ref "U2") (pin "3") (pinfunction "In_3") (pintype "unspecified"))
      (node (ref "U3") (pin "3") (pinfunction "In_3") (pintype "unspecified"))
    )
    (net (code "28") (name "Net-(D7-A)") (class "Default")
      (node (ref "AC5V") (pin "2") (pinfunction "2_2") (pintype "unspecified"))
      (node (ref "D7") (pin "2") (pinfunction "A_2") (pintype "unspecified"))
      (node (ref "D8") (pin "1") (pinfunction "K_1") (pintype "unspecified"))
    )
    (net (code "29") (name "Net-(ESP-WROOM-32-EN)") (class "Default")
      (node (ref "C6") (pin "2") (pinfunction "2_2") (pintype "unspecified"))
      (node (ref "ESP-WROOM-32") (pin "3") (pinfunction "EN_3") (pintype "unspecified"))
      (node (ref "PROG") (pin "3") (pinfunction "3_3") (pintype "unspecified"))
      (node (ref "R9") (pin "2") (pinfunction "2_2") (pintype "unspecified"))
    )
    (net (code "30") (name "Net-(ESP-WROOM-32-IO0)") (class "Default")
      (node (ref "ESP-WROOM-32") (pin "25") (pinfunction "IO0_25") (pintype "unspecified"))
      (node (ref "PROG") (pin "4") (pinfunction "4_4") (pintype "unspecified"))
    )
    (net (code "31") (name "Net-(ESP-WROOM-32-IO2)") (class "Default")
      (node (ref "ESP-WROOM-32") (pin "24") (pinfunction "IO2_24") (pintype "unspecified"))
      (node (ref "H1") (pin "6") (pinfunction "6_6") (pintype "unspecified"))
    )
    (net (code "32") (name "Net-(ESP-WROOM-32-IO4)") (class "Default")
      (node (ref "ESP-WROOM-32") (pin "26") (pinfunction "IO4_26") (pintype "unspecified"))
      (node (ref "H1") (pin "4") (pinfunction "4_4") (pintype "unspecified"))
      (node (ref "H2") (pin "4") (pinfunction "4_4") (pintype "unspecified"))
    )
    (net (code "33") (name "Net-(ESP-WROOM-32-IO13)") (class "Default")
      (node (ref "ESP-WROOM-32") (pin "16") (pinfunction "IO13_16") (pintype "unspecified"))
      (node (ref "H2") (pin "6") (pinfunction "6_6") (pintype "unspecified"))
    )
    (net (code "34") (name "Net-(ESP-WROOM-32-IO16)") (class "Default")
      (node (ref "ESP-WROOM-32") (pin "27") (pinfunction "IO16_27") (pintype "unspecified"))
      (node (ref "H1") (pin "5") (pinfunction "5_5") (pintype "unspecified"))
      (node (ref "H2") (pin "5") (pinfunction "5_5") (pintype "unspecified"))
    )
    (net (code "35") (name "Net-(ESP-WROOM-32-IO17)") (class "Default")
      (node (ref "ESP-WROOM-32") (pin "28") (pinfunction "IO17_28") (pintype "unspecified"))
      (node (ref "H1") (pin "1") (pinfunction "1_1") (pintype "unspecified"))
      (node (ref "H2") (pin "1") (pinfunction "1_1") (pintype "unspecified"))
    )
    (net (code "36") (name "Net-(ESP-WROOM-32-IO18)") (class "Default")
      (node (ref "ESP-WROOM-32") (pin "30") (pinfunction "IO18_30") (pintype "unspecified"))
      (node (ref "H1") (pin "2") (pinfunction "2_2") (pintype "unspecified"))
      (node (ref "H2") (pin "2") (pinfunction "2_2") (pintype "unspecified"))
    )
    (net (code "37") (name "Net-(ESP-WROOM-32-IO21)") (class "Default")
      (node (ref "ESP-WROOM-32") (pin "33") (pinfunction "IO21_33") (pintype "unspecified"))
      (node (ref "R17") (pin "2") (pinfunction "2_2") (pintype "unspecified"))
      (node (ref "U5") (pin "26") (pinfunction "SDA_26") (pintype "unspecified"))
    )
    (net (code "38") (name "Net-(ESP-WROOM-32-IO22)") (class "Default")
      (node (ref "ESP-WROOM-32") (pin "36") (pinfunction "IO22_36") (pintype "unspecified"))
      (node (ref "R16") (pin "2") (pinfunction "2_2") (pintype "unspecified"))
      (node (ref "U5") (pin "25") (pinfunction "SCL_25") (pintype "unspecified"))
    )
    (net (code "39") (name "Net-(ESP-WROOM-32-IO23)") (class "Default")
      (node (ref "ESP-WROOM-32") (pin "37") (pinfunction "IO23_37") (pintype "unspecified"))
      (node (ref "H1") (pin "3") (pinfunction "3_3") (pintype "unspecified"))
      (node (ref "H2") (pin "3") (pinfunction "3_3") (pintype "unspecified"))
    )
    (net (code "40") (name "Net-(ESP-WROOM-32-RXD0)") (class "Default")
      (node (ref "ESP-WROOM-32") (pin "34") (pinfunction "RXD0_34") (pintype "unspecified"))
      (node (ref "PROG") (pin "2") (pinfunction "2_2") (pintype "unspecified"))
    )
    (net (code "41") (name "Net-(ESP-WROOM-32-TXD0)") (class "Default")
      (node (ref "ESP-WROOM-32") (pin "35") (pinfunction "TXD0_35") (pintype "unspecified"))
      (node (ref "PROG") (pin "1") (pinfunction "1_1") (pintype "unspecified"))
    )
    (net (code "42") (name "Net-(R12-Pad1)") (class "Default")
      (node (ref "R12") (pin "1") (pinfunction "1_1") (pintype "unspecified"))
      (node (ref "R3") (pin "3") (pinfunction "3_3") (pintype "input"))
    )
    (net (code "43") (name "Net-(R13-Pad1)") (class "Default")
      (node (ref "R13") (pin "1") (pinfunction "1_1") (pintype "unspecified"))
      (node (ref "R4") (pin "3") (pinfunction "3_3") (pintype "input"))
    )
    (net (code "44") (name "Net-(U5-A1)") (class "Default")
      (node (ref "C7") (pin "2") (pinfunction "2_2") (pintype "unspecified"))
      (node (ref "U4") (pin "2") (pinfunction "2_2") (pintype "unspecified"))
      (node (ref "U5") (pin "1") (pinfunction "A1_1") (pintype "unspecified"))
    )
    (net (code "45") (name "Net-(U5-A2)") (class "Default")
      (node (ref "C8") (pin "2") (pinfunction "2_2") (pintype "unspecified"))
      (node (ref "U5") (pin "2") (pinfunction "A2_2") (pintype "unspecified"))
      (node (ref "U6") (pin "2") (pinfunction "2_2") (pintype "unspecified"))
    )
    (net (code "46") (name "Net-(U5-B1)") (class "Default")
      (node (ref "C9") (pin "2") (pinfunction "2_2") (pintype "unspecified"))
      (node (ref "U5") (pin "3") (pinfunction "B1_3") (pintype "unspecified"))
      (node (ref "U7") (pin "2") (pinfunction "2_2") (pintype "unspecified"))
    )
    (net (code "47") (name "Net-(U5-B2)") (class "Default")
      (node (ref "C10") (pin "2") (pinfunction "2_2") (pintype "unspecified"))
      (node (ref "U10") (pin "2") (pinfunction "2_2") (pintype "unspecified"))
      (node (ref "U5") (pin "4") (pinfunction "B2_4") (pintype "unspecified"))
    )
    (net (code "48") (name "Net-(U5-C1)") (class "Default")
      (node (ref "C11") (pin "2") (pinfunction "2_2") (pintype "unspecified"))
      (node (ref "U12") (pin "2") (pinfunction "2_2") (pintype "unspecified"))
      (node (ref "U5") (pin "5") (pinfunction "C1_5") (pintype "unspecified"))
    )
    (net (code "49") (name "Net-(U5-C2)") (class "Default")
      (node (ref "C12") (pin "2") (pinfunction "2_2") (pintype "unspecified"))
      (node (ref "U13") (pin "2") (pinfunction "2_2") (pintype "unspecified"))
      (node (ref "U5") (pin "6") (pinfunction "C2_6") (pintype "unspecified"))
    )
    (net (code "50") (name "Net-(U5-FIL)") (class "Default")
      (node (ref "C13") (pin "1") (pinfunction "1_1") (pintype "unspecified"))
      (node (ref "U5") (pin "28") (pinfunction "FIL_28") (pintype "unspecified"))
    )
    (net (code "51") (name "Net-(U5-OUTF1)") (class "Default")
      (node (ref "C15") (pin "1") (pinfunction "1_1") (pintype "unspecified"))
      (node (ref "U5") (pin "23") (pinfunction "OUTF1_23") (pintype "unspecified"))
    )
    (net (code "52") (name "Net-(U5-OUTF2)") (class "Default")
      (node (ref "C14") (pin "1") (pinfunction "1_1") (pintype "unspecified"))
      (node (ref "U5") (pin "22") (pinfunction "OUTF2_22") (pintype "unspecified"))
    )
    (net (code "53") (name "Net-(U8-ENB)") (class "Default")
      (node (ref "C25") (pin "2") (pinfunction "2_2") (pintype "unspecified"))
      (node (ref "R1") (pin "1") (pinfunction "1_1") (pintype "input"))
      (node (ref "R14") (pin "1") (pinfunction "1_1") (pintype "unspecified"))
      (node (ref "U8") (pin "6") (pinfunction "ENB_6") (pintype "unspecified"))
      (node (ref "U8") (pin "7") (pinfunction "VPS_7") (pintype "unspecified"))
    )
    (net (code "54") (name "Net-(U8-INM)") (class "Default")
      (node (ref "C22") (pin "1") (pinfunction "1_1") (pintype "unspecified"))
      (node (ref "R8") (pin "1") (pinfunction "1_1") (pintype "unspecified"))
      (node (ref "U8") (pin "1") (pinfunction "INM_1") (pintype "unspecified"))
    )
    (net (code "55") (name "Net-(U8-INP)") (class "Default")
      (node (ref "C22") (pin "2") (pinfunction "2_2") (pintype "unspecified"))
      (node (ref "R7") (pin "1") (pinfunction "1_1") (pintype "unspecified"))
      (node (ref "U8") (pin "8") (pinfunction "INP_8") (pintype "unspecified"))
    )
    (net (code "56") (name "Net-(U8-INT)") (class "Default")
      (node (ref "R1") (pin "2") (pinfunction "2_2") (pintype "input"))
      (node (ref "U8") (pin "5") (pinfunction "INT_5") (pintype "unspecified"))
    )
    (net (code "57") (name "Net-(U8-OFS)") (class "Default")
      (node (ref "C23") (pin "1") (pinfunction "1_1") (pintype "unspecified"))
      (node (ref "U8") (pin "3") (pinfunction "OFS_3") (pintype "unspecified"))
    )
    (net (code "58") (name "Net-(U9-ENB)") (class "Default")
      (node (ref "C31") (pin "2") (pinfunction "2_2") (pintype "unspecified"))
      (node (ref "R15") (pin "1") (pinfunction "1_1") (pintype "unspecified"))
      (node (ref "R2") (pin "1") (pinfunction "1_1") (pintype "input"))
      (node (ref "U9") (pin "6") (pinfunction "ENB_6") (pintype "unspecified"))
      (node (ref "U9") (pin "7") (pinfunction "VPS_7") (pintype "unspecified"))
    )
    (net (code "59") (name "Net-(U9-INM)") (class "Default")
      (node (ref "C28") (pin "1") (pinfunction "1_1") (pintype "unspecified"))
      (node (ref "R18") (pin "1") (pinfunction "1_1") (pintype "unspecified"))
      (node (ref "U9") (pin "1") (pinfunction "INM_1") (pintype "unspecified"))
    )
    (net (code "60") (name "Net-(U9-INP)") (class "Default")
      (node (ref "C28") (pin "2") (pinfunction "2_2") (pintype "unspecified"))
      (node (ref "R10") (pin "1") (pinfunction "1_1") (pintype "unspecified"))
      (node (ref "U9") (pin "8") (pinfunction "INP_8") (pintype "unspecified"))
    )
    (net (code "61") (name "Net-(U9-INT)") (class "Default")
      (node (ref "R2") (pin "2") (pinfunction "2_2") (pintype "input"))
      (node (ref "U9") (pin "5") (pinfunction "INT_5") (pintype "unspecified"))
    )
    (net (code "62") (name "Net-(U9-OFS)") (class "Default")
      (node (ref "C29") (pin "1") (pinfunction "1_1") (pintype "unspecified"))
      (node (ref "U9") (pin "3") (pinfunction "OFS_3") (pintype "unspecified"))
    )
    (net (code "63") (name "OUTF1") (class "Default")
      (node (ref "C15") (pin "2") (pinfunction "2_2") (pintype "unspecified"))
      (node (ref "OUT") (pin "3") (pinfunction "3_3") (pintype "unspecified"))
      (node (ref "R5") (pin "1") (pinfunction "1_1") (pintype "input"))
    )
    (net (code "64") (name "OUTF2") (class "Default")
      (node (ref "C14") (pin "2") (pinfunction "2_2") (pintype "unspecified"))
      (node (ref "OUT") (pin "1") (pinfunction "1_1") (pintype "unspecified"))
      (node (ref "R6") (pin "1") (pinfunction "1_1") (pintype "input"))
    )
    (net (code "65") (name "OUTLOGL") (class "Default")
      (node (ref "C24") (pin "1") (pinfunction "1_1") (pintype "unspecified"))
      (node (ref "ESP-WROOM-32") (pin "7") (pinfunction "IO35_7") (pintype "unspecified"))
      (node (ref "R3") (pin "1") (pinfunction "1_1") (pintype "input"))
      (node (ref "R3") (pin "2") (pinfunction "2_2") (pintype "input"))
      (node (ref "U8") (pin "4") (pinfunction "OUT_4") (pintype "unspecified"))
    )
    (net (code "66") (name "OUTLOGR") (class "Default")
      (node (ref "C30") (pin "1") (pinfunction "1_1") (pintype "unspecified"))
      (node (ref "ESP-WROOM-32") (pin "6") (pinfunction "IO34_6") (pintype "unspecified"))
      (node (ref "R4") (pin "1") (pinfunction "1_1") (pintype "input"))
      (node (ref "R4") (pin "2") (pinfunction "2_2") (pintype "input"))
      (node (ref "U9") (pin "4") (pinfunction "OUT_4") (pintype "unspecified"))
    )
    (net (code "67") (name "RDR") (class "Default")
      (node (ref "U3") (pin "4") (pinfunction "TAB_4") (pintype "unspecified"))
    )
    (net (code "68") (name "unconnected-(ESP-WROOM-32-CLK-Pad20)") (class "Default")
      (node (ref "ESP-WROOM-32") (pin "20") (pinfunction "CLK_20") (pintype "unspecified"))
    )
    (net (code "69") (name "unconnected-(ESP-WROOM-32-CMD-Pad19)") (class "Default")
      (node (ref "ESP-WROOM-32") (pin "19") (pinfunction "CMD_19") (pintype "unspecified"))
    )
    (net (code "70") (name "unconnected-(ESP-WROOM-32-GND-Pad1)") (class "Default")
      (node (ref "ESP-WROOM-32") (pin "1") (pinfunction "GND_1") (pintype "unspecified"))
    )
    (net (code "71") (name "unconnected-(ESP-WROOM-32-GND-Pad15)") (class "Default")
      (node (ref "ESP-WROOM-32") (pin "15") (pinfunction "GND_15") (pintype "unspecified"))
    )
    (net (code "72") (name "unconnected-(ESP-WROOM-32-IO5-Pad29)") (class "Default")
      (node (ref "ESP-WROOM-32") (pin "29") (pinfunction "IO5_29") (pintype "unspecified"))
    )
    (net (code "73") (name "unconnected-(ESP-WROOM-32-IO12-Pad14)") (class "Default")
      (node (ref "ESP-WROOM-32") (pin "14") (pinfunction "IO12_14") (pintype "unspecified"))
    )
    (net (code "74") (name "unconnected-(ESP-WROOM-32-IO15-Pad23)") (class "Default")
      (node (ref "ESP-WROOM-32") (pin "23") (pinfunction "IO15_23") (pintype "unspecified"))
    )
    (net (code "75") (name "unconnected-(ESP-WROOM-32-IO19-Pad31)") (class "Default")
      (node (ref "ESP-WROOM-32") (pin "31") (pinfunction "IO19_31") (pintype "unspecified"))
    )
    (net (code "76") (name "unconnected-(ESP-WROOM-32-IO32-Pad8)") (class "Default")
      (node (ref "ESP-WROOM-32") (pin "8") (pinfunction "IO32_8") (pintype "unspecified"))
    )
    (net (code "77") (name "unconnected-(ESP-WROOM-32-NC-Pad32)") (class "Default")
      (node (ref "ESP-WROOM-32") (pin "32") (pinfunction "NC_32") (pintype "unspecified"))
    )
    (net (code "78") (name "unconnected-(ESP-WROOM-32-SD0-Pad21)") (class "Default")
      (node (ref "ESP-WROOM-32") (pin "21") (pinfunction "SD0_21") (pintype "unspecified"))
    )
    (net (code "79") (name "unconnected-(ESP-WROOM-32-SD1-Pad22)") (class "Default")
      (node (ref "ESP-WROOM-32") (pin "22") (pinfunction "SD1_22") (pintype "unspecified"))
    )
    (net (code "80") (name "unconnected-(ESP-WROOM-32-SD2-Pad17)") (class "Default")
      (node (ref "ESP-WROOM-32") (pin "17") (pinfunction "SD2_17") (pintype "unspecified"))
    )
    (net (code "81") (name "unconnected-(ESP-WROOM-32-SD3-Pad18)") (class "Default")
      (node (ref "ESP-WROOM-32") (pin "18") (pinfunction "SD3_18") (pintype "unspecified"))
    )
    (net (code "82") (name "unconnected-(ESP-WROOM-32-SENSOR_VN-Pad5)") (class "Default")
      (node (ref "ESP-WROOM-32") (pin "5") (pinfunction "SENSOR_VN_5") (pintype "unspecified"))
    )
    (net (code "83") (name "unconnected-(ESP-WROOM-32-SENSOR_VP-Pad4)") (class "Default")
      (node (ref "ESP-WROOM-32") (pin "4") (pinfunction "SENSOR_VP_4") (pintype "unspecified"))
    )
    (net (code "84") (name "unconnected-(U2-TAB-Pad4)") (class "Default")
      (node (ref "U2") (pin "4") (pinfunction "TAB_4") (pintype "unspecified"))
    )
    (net (code "85") (name "unconnected-(U5-DN-Pad8)") (class "Default")
      (node (ref "U5") (pin "8") (pinfunction "DN_8") (pintype "unspecified"))
    )
    (net (code "86") (name "unconnected-(U5-DP1-Pad7)") (class "Default")
      (node (ref "U5") (pin "7") (pinfunction "DP1_7") (pintype "unspecified"))
    )
    (net (code "87") (name "unconnected-(U5-DP2-Pad9)") (class "Default")
      (node (ref "U5") (pin "9") (pinfunction "DP2_9") (pintype "unspecified"))
    )
    (net (code "88") (name "unconnected-(U5-EN1-Pad11)") (class "Default")
      (node (ref "U5") (pin "11") (pinfunction "EN1_11") (pintype "unspecified"))
    )
    (net (code "89") (name "unconnected-(U5-EN2-Pad12)") (class "Default")
      (node (ref "U5") (pin "12") (pinfunction "EN2_12") (pintype "unspecified"))
    )
    (net (code "90") (name "unconnected-(U5-EP1-Pad10)") (class "Default")
      (node (ref "U5") (pin "10") (pinfunction "EP1_10") (pintype "unspecified"))
    )
    (net (code "91") (name "unconnected-(U5-EP2-Pad13)") (class "Default")
      (node (ref "U5") (pin "13") (pinfunction "EP2_13") (pintype "unspecified"))
    )
    (net (code "92") (name "unconnected-(U5-LOUT-Pad17)") (class "Default")
      (node (ref "U5") (pin "17") (pinfunction "LOUT_17") (pintype "unspecified"))
    )
    (net (code "93") (name "unconnected-(U5-LRST-Pad16)") (class "Default")
      (node (ref "U5") (pin "16") (pinfunction "LRST_16") (pintype "unspecified"))
    )
    (net (code "94") (name "unconnected-(U5-MIN-Pad14)") (class "Default")
      (node (ref "U5") (pin "14") (pinfunction "MIN_14") (pintype "unspecified"))
    )
    (net (code "95") (name "unconnected-(U5-MUTE-Pad15)") (class "Default")
      (node (ref "U5") (pin "15") (pinfunction "MUTE_15") (pintype "unspecified"))
    )
    (net (code "96") (name "unconnected-(U5-OUTR1-Pad21)") (class "Default")
      (node (ref "U5") (pin "21") (pinfunction "OUTR1_21") (pintype "unspecified"))
    )
    (net (code "97") (name "unconnected-(U5-OUTR2-Pad20)") (class "Default")
      (node (ref "U5") (pin "20") (pinfunction "OUTR2_20") (pintype "unspecified"))
    )
    (net (code "98") (name "unconnected-(U5-OUTS1-Pad19)") (class "Default")
      (node (ref "U5") (pin "19") (pinfunction "OUTS1_19") (pintype "unspecified"))
    )
    (net (code "99") (name "unconnected-(U5-OUTS2-Pad18)") (class "Default")
      (node (ref "U5") (pin "18") (pinfunction "OUTS2_18") (pintype "unspecified"))
    )
    (net (code "100") (name "unconnected-(U11-Pad1)") (class "Default")
      (node (ref "U11") (pin "1") (pinfunction "1_1") (pintype "unspecified"))
    )
  )
)
